# DANI-PROJECT.net
KiCad netlist of a schematic drawn in EAGLE
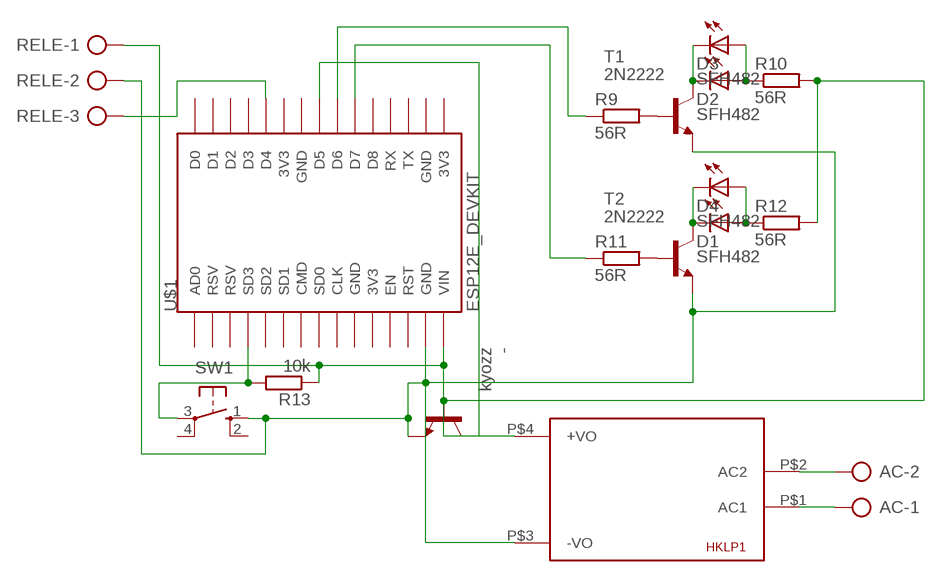
[diagram p0: schematic, sheet 1]

(export (version "E")
  (design (tool "Eeschema 10.0.6"))
  (components
    (comp (ref "-")
      (value "kyozz")
      (footprint "eagle-import:TO92-EBC")
      (libsource (lib "eagle-import") (part "BC489"))
    )
    (comp (ref "AC")
      (value "AK500/2-H")
      (footprint "eagle-import:AK500_2-H")
      (libsource (lib "eagle-import") (part "AK500/2-H"))
    )
    (comp (ref "D1")
      (value "SFH482")
      (footprint "eagle-import:SFH482")
      (libsource (lib "eagle-import") (part "SFH482"))
    )
    (comp (ref "D2")
      (value "SFH482")
      (footprint "eagle-import:SFH482")
      (libsource (lib "eagle-import") (part "SFH482"))
    )
    (comp (ref "D3")
      (value "SFH482")
      (footprint "eagle-import:SFH482")
      (libsource (lib "eagle-import") (part "SFH482"))
    )
    (comp (ref "D4")
      (value "SFH482")
      (footprint "eagle-import:SFH482")
      (libsource (lib "eagle-import") (part "SFH482"))
    )
    (comp (ref "HKLP1")
      (value "HKLPM01")
      (footprint "eagle-import:HKLPM01")
      (libsource (lib "eagle-import") (part "HKLPM01"))
    )
    (comp (ref "R9")
      (value "56R")
      (footprint "eagle-import:0207_7")
      (libsource (lib "eagle-import") (part "R-EU_0207/7"))
    )
    (comp (ref "R10")
      (value "56R")
      (footprint "eagle-import:0207_7")
      (libsource (lib "eagle-import") (part "R-EU_0207/7"))
    )
    (comp (ref "R11")
      (value "56R")
      (footprint "eagle-import:0207_7")
      (libsource (lib "eagle-import") (part "R-EU_0207/7"))
    )
    (comp (ref "R12")
      (value "56R")
      (footprint "eagle-import:0207_7")
      (libsource (lib "eagle-import") (part "R-EU_0207/7"))
    )
    (comp (ref "R13")
      (value "10k")
      (footprint "eagle-import:0207_7")
      (libsource (lib "eagle-import") (part "R-EU_0207/7"))
    )
    (comp (ref "RELE")
      (value "AK500/3-H")
      (footprint "eagle-import:AK500_3-H")
      (libsource (lib "eagle-import") (part "AK500/3-H"))
    )
    (comp (ref "SW1")
      (value "10-XX")
      (footprint "eagle-import:B3F-10XX")
      (libsource (lib "eagle-import") (part "10-XX"))
    )
    (comp (ref "T1")
      (value "2N2222")
      (footprint "eagle-import:TO18")
      (libsource (lib "eagle-import") (part "2N2222"))
    )
    (comp (ref "T2")
      (value "2N2222")
      (footprint "eagle-import:TO18")
      (libsource (lib "eagle-import") (part "2N2222"))
    )
    (comp (ref "U$1")
      (value "ESP12E_DEVKIT")
      (footprint "eagle-import:ESP12E_DEVKIT")
      (libsource (lib "eagle-import") (part "ESP12E_DEVKIT"))
    )
  )
  (nets
    (net (code "1") (name "Net-(--PadC)") (class "Default")
      (node (ref "-") (pin "C") (pinfunction "C_C") (pintype "passive"))
      (node (ref "U$1") (pin "D5") (pinfunction "D5_D5") (pintype "bidirectional"))
    )
    (net (code "2") (name "Net-(ACA-KL)") (class "Default")
      (node (ref "AC") (pin "1") (pinfunction "KL_1") (pintype "passive"))
      (node (ref "HKLP1") (pin "P$1") (pinfunction "AC1_P$1") (pintype "bidirectional"))
    )
    (net (code "3") (name "Net-(ACB-KL)") (class "Default")
      (node (ref "AC") (pin "2") (pinfunction "KL_2") (pintype "passive"))
      (node (ref "HKLP1") (pin "P$2") (pinfunction "AC2_P$2") (pintype "bidirectional"))
    )
    (net (code "4") (name "Net-(D1-C)") (class "Default")
      (node (ref "D1") (pin "K") (pinfunction "C_K") (pintype "passive"))
      (node (ref "D4") (pin "K") (pinfunction "C_K") (pintype "passive"))
      (node (ref "T2") (pin "3") (pinfunction "C_3") (pintype "passive"))
    )
    (net (code "5") (name "Net-(D1-PadA)") (class "Default")
      (node (ref "D1") (pin "A") (pinfunction "A_A") (pintype "passive"))
      (node (ref "D4") (pin "A") (pinfunction "A_A") (pintype "passive"))
      (node (ref "R12") (pin "1") (pinfunction "1_1") (pintype "passive"))
    )
    (net (code "6") (name "Net-(D2-C)") (class "Default")
      (node (ref "D2") (pin "K") (pinfunction "C_K") (pintype "passive"))
      (node (ref "D3") (pin "K") (pinfunction "C_K") (pintype "passive"))
      (node (ref "T1") (pin "3") (pinfunction "C_3") (pintype "passive"))
    )
    (net (code "7") (name "Net-(D2-PadA)") (class "Default")
      (node (ref "D2") (pin "A") (pinfunction "A_A") (pintype "passive"))
      (node (ref "D3") (pin "A") (pinfunction "A_A") (pintype "passive"))
      (node (ref "R10") (pin "1") (pinfunction "1_1") (pintype "passive"))
    )
    (net (code "8") (name "Net-(HKLP1-+VO)") (class "Default")
      (node (ref "-") (pin "B") (pinfunction "B_B") (pintype "passive"))
      (node (ref "HKLP1") (pin "P$4") (pinfunction "+VO_P$4") (pintype "bidirectional"))
      (node (ref "R10") (pin "2") (pinfunction "2_2") (pintype "passive"))
      (node (ref "R12") (pin "2") (pinfunction "2_2") (pintype "passive"))
      (node (ref "R13") (pin "1") (pinfunction "1_1") (pintype "passive"))
      (node (ref "RELE") (pin "1") (pinfunction "KL_1") (pintype "passive"))
      (node (ref "U$1") (pin "VIN") (pinfunction "VIN_VIN") (pintype "bidirectional"))
    )
    (net (code "9") (name "Net-(HKLP1--VO)") (class "Default")
      (node (ref "-") (pin "E") (pinfunction "E_E") (pintype "passive"))
      (node (ref "HKLP1") (pin "P$3") (pinfunction "-VO_P$3") (pintype "bidirectional"))
      (node (ref "RELE") (pin "2") (pinfunction "KL_2") (pintype "passive"))
      (node (ref "SW1") (pin "1") (pinfunction "S_1") (pintype "passive"))
      (node (ref "T1") (pin "1") (pinfunction "E_1") (pintype "passive"))
      (node (ref "T2") (pin "1") (pinfunction "E_1") (pintype "passive"))
      (node (ref "U$1") (pin "GND@1") (pinfunction "GND_GND@1") (pintype "bidirectional"))
    )
    (net (code "10") (name "Net-(R9-Pad1)") (class "Default")
      (node (ref "R9") (pin "1") (pinfunction "1_1") (pintype "passive"))
      (node (ref "U$1") (pin "D6") (pinfunction "D6_D6") (pintype "bidirectional"))
    )
    (net (code "11") (name "Net-(R11-Pad1)") (class "Default")
      (node (ref "R11") (pin "1") (pinfunction "1_1") (pintype "passive"))
      (node (ref "U$1") (pin "D7") (pinfunction "D7_D7") (pintype "bidirectional"))
    )
    (net (code "12") (name "Net-(RELEC-KL)") (class "Default")
      (node (ref "RELE") (pin "3") (pinfunction "KL_3") (pintype "passive"))
      (node (ref "U$1") (pin "D4") (pinfunction "D4_D4") (pintype "bidirectional"))
    )
    (net (code "13") (name "Net-(SW1-P)") (class "Default")
      (node (ref "R13") (pin "2") (pinfunction "2_2") (pintype "passive"))
      (node (ref "SW1") (pin "3") (pinfunction "P_3") (pintype "passive"))
      (node (ref "U$1") (pin "SD3") (pinfunction "SD3_SD3") (pintype "bidirectional"))
    )
    (net (code "14") (name "Net-(T1-B)") (class "Default")
      (node (ref "R9") (pin "2") (pinfunction "2_2") (pintype "passive"))
      (node (ref "T1") (pin "2") (pinfunction "B_2") (pintype "passive"))
    )
    (net (code "15") (name "Net-(T2-B)") (class "Default")
      (node (ref "R11") (pin "2") (pinfunction "2_2") (pintype "passive"))
      (node (ref "T2") (pin "2") (pinfunction "B_2") (pintype "passive"))
    )
    (net (code "16") (name "unconnected-(SW1-P1-Pad4)") (class "Default")
      (node (ref "SW1") (pin "4") (pinfunction "P1_4") (pintype "passive"))
    )
    (net (code "17") (name "unconnected-(SW1-S1-Pad2)") (class "Default")
      (node (ref "SW1") (pin "2") (pinfunction "S1_2") (pintype "passive"))
    )
    (net (code "18") (name "unconnected-(U$1-3V3-Pad3V3@0)") (class "Default")
      (node (ref "U$1") (pin "3V3@0") (pinfunction "3V3_3V3@0") (pintype "bidirectional"))
    )
    (net (code "19") (name "unconnected-(U$1-3V3-Pad3V3@1)") (class "Default")
      (node (ref "U$1") (pin "3V3@1") (pinfunction "3V3_3V3@1") (pintype "bidirectional"))
    )
    (net (code "20") (name "unconnected-(U$1-3V3-Pad3V3@2)") (class "Default")
      (node (ref "U$1") (pin "3V3@2") (pinfunction "3V3_3V3@2") (pintype "bidirectional"))
    )
    (net (code "21") (name "unconnected-(U$1-GND-PadGND@0)") (class "Default")
      (node (ref "U$1") (pin "GND@0") (pinfunction "GND_GND@0") (pintype "bidirectional"))
    )
    (net (code "22") (name "unconnected-(U$1-GND-PadGND@2)") (class "Default")
      (node (ref "U$1") (pin "GND@2") (pinfunction "GND_GND@2") (pintype "bidirectional"))
    )
    (net (code "23") (name "unconnected-(U$1-GND-PadGND@3)") (class "Default")
      (node (ref "U$1") (pin "GND@3") (pinfunction "GND_GND@3") (pintype "bidirectional"))
    )
    (net (code "24") (name "unconnected-(U$1-PadAD0)") (class "Default")
      (node (ref "U$1") (pin "AD0") (pinfunction "AD0_AD0") (pintype "bidirectional"))
    )
    (net (code "25") (name "unconnected-(U$1-PadCLK)") (class "Default")
      (node (ref "U$1") (pin "CLK") (pinfunction "CLK_CLK") (pintype "bidirectional"))
    )
    (net (code "26") (name "unconnected-(U$1-PadCMD)") (class "Default")
      (node (ref "U$1") (pin "CMD") (pinfunction "CMD_CMD") (pintype "bidirectional"))
    )
    (net (code "27") (name "unconnected-(U$1-PadD0)") (class "Default")
      (node (ref "U$1") (pin "D0") (pinfunction "D0_D0") (pintype "bidirectional"))
    )
    (net (code "28") (name "unconnected-(U$1-PadD1)") (class "Default")
      (node (ref "U$1") (pin "D1") (pinfunction "D1_D1") (pintype "bidirectional"))
    )
    (net (code "29") (name "unconnected-(U$1-PadD2)") (class "Default")
      (node (ref "U$1") (pin "D2") (pinfunction "D2_D2") (pintype "bidirectional"))
    )
    (net (code "30") (name "unconnected-(U$1-PadD3)") (class "Default")
      (node (ref "U$1") (pin "D3") (pinfunction "D3_D3") (pintype "bidirectional"))
    )
    (net (code "31") (name "unconnected-(U$1-PadD8)") (class "Default")
      (node (ref "U$1") (pin "D8") (pinfunction "D8_D8") (pintype "bidirectional"))
    )
    (net (code "32") (name "unconnected-(U$1-PadEN)") (class "Default")
      (node (ref "U$1") (pin "EN") (pinfunction "EN_EN") (pintype "bidirectional"))
    )
    (net (code "33") (name "unconnected-(U$1-PadRST)") (class "Default")
      (node (ref "U$1") (pin "RST") (pinfunction "RST_RST") (pintype "bidirectional"))
    )
    (net (code "34") (name "unconnected-(U$1-PadRX)") (class "Default")
      (node (ref "U$1") (pin "RX") (pinfunction "RX_RX") (pintype "bidirectional"))
    )
    (net (code "35") (name "unconnected-(U$1-PadSD0)") (class "Default")
      (node (ref "U$1") (pin "SD0") (pinfunction "SD0_SD0") (pintype "bidirectional"))
    )
    (net (code "36") (name "unconnected-(U$1-PadSD1)") (class "Default")
      (node (ref "U$1") (pin "SD1") (pinfunction "SD1_SD1") (pintype "bidirectional"))
    )
    (net (code "37") (name "unconnected-(U$1-PadSD2)") (class "Default")
      (node (ref "U$1") (pin "SD2") (pinfunction "SD2_SD2") (pintype "bidirectional"))
    )
    (net (code "38") (name "unconnected-(U$1-PadTX)") (class "Default")
      (node (ref "U$1") (pin "TX") (pinfunction "TX_TX") (pintype "bidirectional"))
    )
    (net (code "39") (name "unconnected-(U$1-RSV-PadRSV@0)") (class "Default")
      (node (ref "U$1") (pin "RSV@0") (pinfunction "RSV_RSV@0") (pintype "bidirectional"))
    )
    (net (code "40") (name "unconnected-(U$1-RSV-PadRSV@1)") (class "Default")
      (node (ref "U$1") (pin "RSV@1") (pinfunction "RSV_RSV@1") (pintype "bidirectional"))
    )
  )
)
